# SilentStepStick-TMC2100_v20_5V.net
KiCad netlist of a schematic drawn in EAGLE
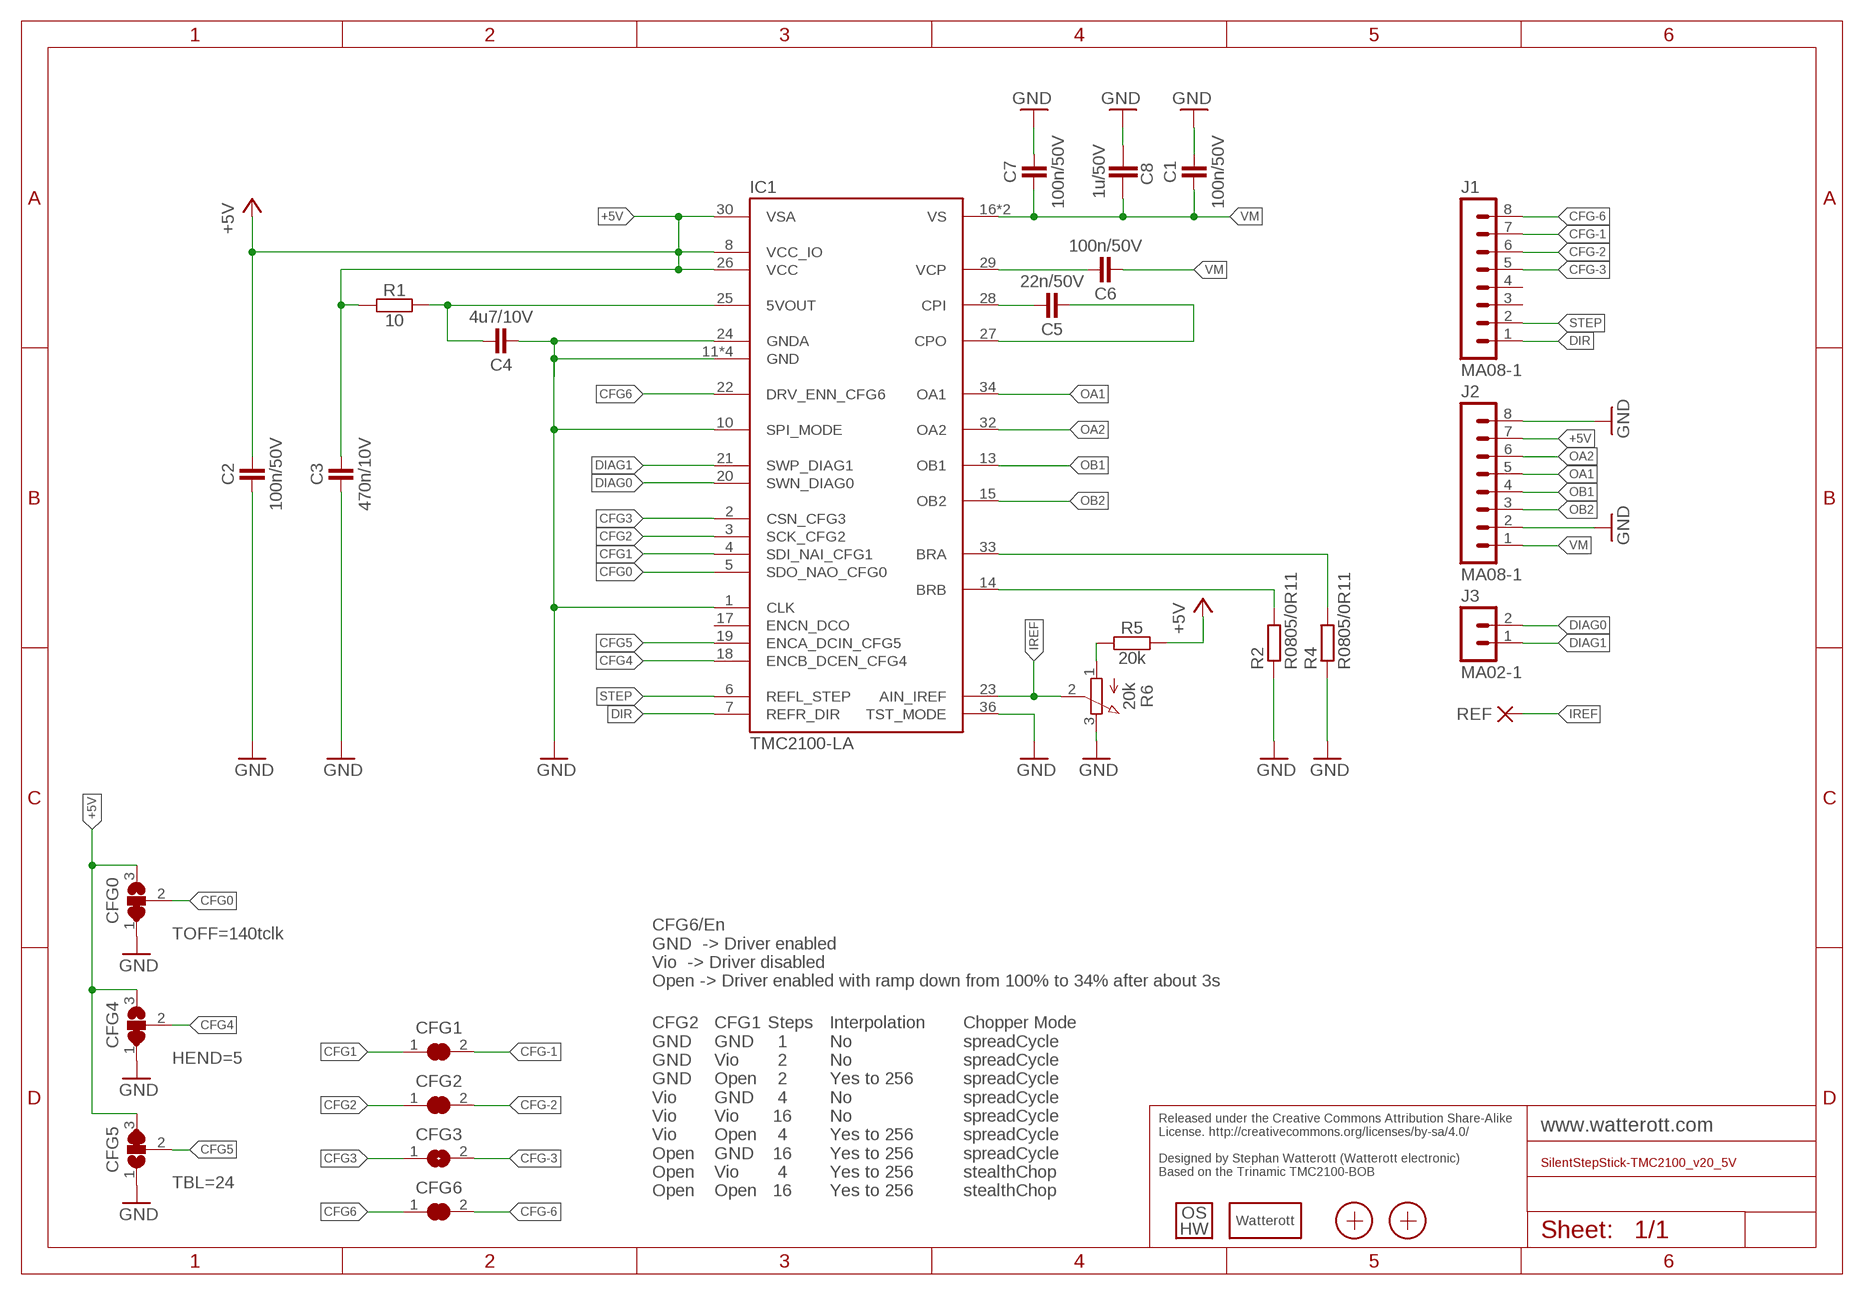
[diagram p0: schematic, sheet 1]

(export (version "E")
  (design (tool "Eeschema 10.0.6"))
  (components
    (comp (ref "C1")
      (value "100n/50V")
      (footprint "eagle-import:C0402")
      (libsource (lib "eagle-import") (part "CAPACITOR-0402"))
    )
    (comp (ref "C2")
      (value "100n/50V")
      (footprint "eagle-import:C0402")
      (libsource (lib "eagle-import") (part "CAPACITOR-0402"))
    )
    (comp (ref "C3")
      (value "470n/10V")
      (footprint "eagle-import:C0402")
      (libsource (lib "eagle-import") (part "CAPACITOR-0402"))
    )
    (comp (ref "C4")
      (value "4u7/10V")
      (footprint "eagle-import:C0402")
      (libsource (lib "eagle-import") (part "CAPACITOR-0402"))
    )
    (comp (ref "C5")
      (value "22n/50V")
      (footprint "eagle-import:C0402")
      (libsource (lib "eagle-import") (part "CAPACITOR-0402"))
    )
    (comp (ref "C6")
      (value "100n/50V")
      (footprint "eagle-import:C0402")
      (libsource (lib "eagle-import") (part "CAPACITOR-0402"))
    )
    (comp (ref "C7")
      (value "100n/50V")
      (footprint "eagle-import:C0402")
      (libsource (lib "eagle-import") (part "CAPACITOR-0402"))
    )
    (comp (ref "C8")
      (value "1u/50V")
      (footprint "eagle-import:C0603")
      (libsource (lib "eagle-import") (part "C-EUC0603"))
    )
    (comp (ref "CFG0")
      (value "JUMPER3-0201")
      (footprint "eagle-import:JUMPER3-0201")
      (libsource (lib "eagle-import") (part "JUMPER3-0201"))
    )
    (comp (ref "CFG1")
      (value "JUMPER2-0201")
      (footprint "eagle-import:JUMPER2-0201")
      (libsource (lib "eagle-import") (part "JUMPER2-0201"))
    )
    (comp (ref "CFG2")
      (value "JUMPER2-0201")
      (footprint "eagle-import:JUMPER2-0201")
      (libsource (lib "eagle-import") (part "JUMPER2-0201"))
    )
    (comp (ref "CFG3")
      (value "JUMPER2-0201")
      (footprint "eagle-import:JUMPER2-0201")
      (libsource (lib "eagle-import") (part "JUMPER2-0201"))
    )
    (comp (ref "CFG4")
      (value "JUMPER3-0201")
      (footprint "eagle-import:JUMPER3-0201")
      (libsource (lib "eagle-import") (part "JUMPER3-0201"))
    )
    (comp (ref "CFG5")
      (value "JUMPER3-0201")
      (footprint "eagle-import:JUMPER3-0201")
      (libsource (lib "eagle-import") (part "JUMPER3-0201"))
    )
    (comp (ref "CFG6")
      (value "JUMPER2-0201")
      (footprint "eagle-import:JUMPER2-0201")
      (libsource (lib "eagle-import") (part "JUMPER2-0201"))
    )
    (comp (ref "IC1")
      (value "TMC2100-LA")
      (footprint "eagle-import:QFN36-PAD")
      (libsource (lib "eagle-import") (part "TMC21X0-LA"))
    )
    (comp (ref "J1")
      (value "MA08-1")
      (footprint "eagle-import:MA08-1")
      (libsource (lib "eagle-import") (part "MA08-1"))
    )
    (comp (ref "J2")
      (value "MA08-1")
      (footprint "eagle-import:MA08-1")
      (libsource (lib "eagle-import") (part "MA08-1"))
    )
    (comp (ref "J3")
      (value "MA02-1")
      (footprint "eagle-import:MA02-1")
      (libsource (lib "eagle-import") (part "MA02-1"))
    )
    (comp (ref "LOGO3")
      (value "LOGO_SPARK-2")
      (footprint "eagle-import:SPARK_2MM")
      (libsource (lib "eagle-import") (part "LOGO_SPARK-2"))
    )
    (comp (ref "LOGO4")
      (value "LOGO_OSHW-2")
      (footprint "eagle-import:OSHW_2MM")
      (libsource (lib "eagle-import") (part "LOGO_OSHW-2"))
    )
    (comp (ref "R1")
      (value "10")
      (footprint "eagle-import:C0402")
      (libsource (lib "eagle-import") (part "RESISTOR-0402"))
    )
    (comp (ref "R2")
      (value "R0805/0R11")
      (footprint "eagle-import:M0805")
      (libsource (lib "eagle-import") (part "R-EU_M0805"))
    )
    (comp (ref "R4")
      (value "R0805/0R11")
      (footprint "eagle-import:M0805")
      (libsource (lib "eagle-import") (part "R-EU_M0805"))
    )
    (comp (ref "R5")
      (value "20k")
      (footprint "eagle-import:C0402")
      (libsource (lib "eagle-import") (part "RESISTOR-0402"))
    )
    (comp (ref "R6")
      (value "20k")
      (footprint "eagle-import:POT_EVM3R")
      (libsource (lib "eagle-import") (part "POT-EVM3R"))
    )
    (comp (ref "REF")
      (value "PAD-0.6-1.1")
      (footprint "eagle-import:PAD-0.6-1.1")
      (libsource (lib "eagle-import") (part "PAD-0.6-1.1"))
    )
    (comp (ref "X1")
      (value "PASSER-07")
      (footprint "eagle-import:PASSER_07MM")
      (libsource (lib "eagle-import") (part "PASSER-07"))
    )
    (comp (ref "X2")
      (value "PASSER-07")
      (footprint "eagle-import:PASSER_07MM")
      (libsource (lib "eagle-import") (part "PASSER-07"))
    )
  )
  (nets
    (net (code "1") (name "+5V") (class "Default")
      (node (ref "C2") (pin "2") (pinfunction "2_2") (pintype "passive"))
      (node (ref "C3") (pin "2") (pinfunction "2_2") (pintype "passive"))
      (node (ref "CFG0") (pin "3") (pinfunction "3_3") (pintype "passive"))
      (node (ref "CFG4") (pin "3") (pinfunction "3_3") (pintype "passive"))
      (node (ref "CFG5") (pin "3") (pinfunction "3_3") (pintype "passive"))
      (node (ref "IC1") (pin "26") (pinfunction "VCC_26") (pintype "power_in"))
      (node (ref "IC1") (pin "30") (pinfunction "VSA_30") (pintype "power_in"))
      (node (ref "IC1") (pin "8") (pinfunction "VCC_IO_8") (pintype "power_in"))
      (node (ref "J2") (pin "7") (pinfunction "7_7") (pintype "passive"))
      (node (ref "R1") (pin "1") (pinfunction "1_1") (pintype "passive"))
      (node (ref "R5") (pin "2") (pinfunction "2_2") (pintype "passive"))
    )
    (net (code "2") (name "CFG-1") (class "Default")
      (node (ref "CFG1") (pin "2") (pinfunction "2_2") (pintype "passive"))
      (node (ref "J1") (pin "7") (pinfunction "7_7") (pintype "passive"))
    )
    (net (code "3") (name "CFG-2") (class "Default")
      (node (ref "CFG2") (pin "2") (pinfunction "2_2") (pintype "passive"))
      (node (ref "J1") (pin "6") (pinfunction "6_6") (pintype "passive"))
    )
    (net (code "4") (name "CFG-3") (class "Default")
      (node (ref "CFG3") (pin "2") (pinfunction "2_2") (pintype "passive"))
      (node (ref "J1") (pin "5") (pinfunction "5_5") (pintype "passive"))
    )
    (net (code "5") (name "CFG-6") (class "Default")
      (node (ref "CFG6") (pin "2") (pinfunction "2_2") (pintype "passive"))
      (node (ref "J1") (pin "8") (pinfunction "8_8") (pintype "passive"))
    )
    (net (code "6") (name "CFG0") (class "Default")
      (node (ref "CFG0") (pin "2") (pinfunction "2_2") (pintype "passive"))
      (node (ref "IC1") (pin "5") (pinfunction "SDO_NAO_CFG0_5") (pintype "bidirectional"))
    )
    (net (code "7") (name "CFG1") (class "Default")
      (node (ref "CFG1") (pin "1") (pinfunction "1_1") (pintype "passive"))
      (node (ref "IC1") (pin "4") (pinfunction "SDI_NAI_CFG1_4") (pintype "bidirectional"))
    )
    (net (code "8") (name "CFG2") (class "Default")
      (node (ref "CFG2") (pin "1") (pinfunction "1_1") (pintype "passive"))
      (node (ref "IC1") (pin "3") (pinfunction "SCK_CFG2_3") (pintype "bidirectional"))
    )
    (net (code "9") (name "CFG3") (class "Default")
      (node (ref "CFG3") (pin "1") (pinfunction "1_1") (pintype "passive"))
      (node (ref "IC1") (pin "2") (pinfunction "CSN_CFG3_2") (pintype "bidirectional"))
    )
    (net (code "10") (name "CFG4") (class "Default")
      (node (ref "CFG4") (pin "2") (pinfunction "2_2") (pintype "passive"))
      (node (ref "IC1") (pin "18") (pinfunction "ENCB_DCEN_CFG4_18") (pintype "bidirectional"))
    )
    (net (code "11") (name "CFG5") (class "Default")
      (node (ref "CFG5") (pin "2") (pinfunction "2_2") (pintype "passive"))
      (node (ref "IC1") (pin "19") (pinfunction "ENCA_DCIN_CFG5_19") (pintype "bidirectional"))
    )
    (net (code "12") (name "CFG6") (class "Default")
      (node (ref "CFG6") (pin "1") (pinfunction "1_1") (pintype "passive"))
      (node (ref "IC1") (pin "22") (pinfunction "DRV_ENN_CFG6_22") (pintype "bidirectional"))
    )
    (net (code "13") (name "DIAG0") (class "Default")
      (node (ref "IC1") (pin "20") (pinfunction "SWN_DIAG0_20") (pintype "bidirectional"))
      (node (ref "J3") (pin "2") (pinfunction "2_2") (pintype "passive"))
    )
    (net (code "14") (name "DIAG1") (class "Default")
      (node (ref "IC1") (pin "21") (pinfunction "SWP_DIAG1_21") (pintype "bidirectional"))
      (node (ref "J3") (pin "1") (pinfunction "1_1") (pintype "passive"))
    )
    (net (code "15") (name "DIR") (class "Default")
      (node (ref "IC1") (pin "7") (pinfunction "REFR_DIR_7") (pintype "bidirectional"))
      (node (ref "J1") (pin "1") (pinfunction "1_1") (pintype "passive"))
    )
    (net (code "16") (name "GND") (class "Default")
      (node (ref "C1") (pin "2") (pinfunction "2_2") (pintype "passive"))
      (node (ref "C2") (pin "1") (pinfunction "1_1") (pintype "passive"))
      (node (ref "C3") (pin "1") (pinfunction "1_1") (pintype "passive"))
      (node (ref "C4") (pin "1") (pinfunction "1_1") (pintype "passive"))
      (node (ref "C7") (pin "2") (pinfunction "2_2") (pintype "passive"))
      (node (ref "C8") (pin "2") (pinfunction "2_2") (pintype "passive"))
      (node (ref "CFG0") (pin "1") (pinfunction "1_1") (pintype "passive"))
      (node (ref "CFG4") (pin "1") (pinfunction "1_1") (pintype "passive"))
      (node (ref "CFG5") (pin "1") (pinfunction "1_1") (pintype "passive"))
      (node (ref "IC1") (pin "1") (pinfunction "CLK_1") (pintype "bidirectional"))
      (node (ref "IC1") (pin "10") (pinfunction "SPI_MODE_10") (pintype "bidirectional"))
      (node (ref "IC1") (pin "11") (pinfunction "GND_11") (pintype "power_in"))
      (node (ref "IC1") (pin "12") (pinfunction "GND_12") (pintype "power_in"))
      (node (ref "IC1") (pin "24") (pinfunction "GNDA_24") (pintype "power_in"))
      (node (ref "IC1") (pin "35") (pinfunction "GND_35") (pintype "power_in"))
      (node (ref "IC1") (pin "36") (pinfunction "TST_MODE_36") (pintype "bidirectional"))
      (node (ref "IC1") (pin "TP") (pinfunction "GND_TP") (pintype "power_in"))
      (node (ref "J2") (pin "2") (pinfunction "2_2") (pintype "passive"))
      (node (ref "J2") (pin "8") (pinfunction "8_8") (pintype "passive"))
      (node (ref "R2") (pin "1") (pinfunction "1_1") (pintype "passive"))
      (node (ref "R4") (pin "1") (pinfunction "1_1") (pintype "passive"))
      (node (ref "R6") (pin "3") (pinfunction "E_3") (pintype "passive"))
    )
    (net (code "17") (name "IREF") (class "Default")
      (node (ref "IC1") (pin "23") (pinfunction "AIN_IREF_23") (pintype "passive"))
      (node (ref "R6") (pin "2") (pinfunction "S_2") (pintype "passive"))
      (node (ref "REF") (pin "1") (pinfunction "P_1") (pintype "passive"))
    )
    (net (code "18") (name "Net-(IC1-5VOUT)") (class "Default")
      (node (ref "C4") (pin "2") (pinfunction "2_2") (pintype "passive"))
      (node (ref "IC1") (pin "25") (pinfunction "5VOUT_25") (pintype "power_in"))
      (node (ref "R1") (pin "2") (pinfunction "2_2") (pintype "passive"))
    )
    (net (code "19") (name "Net-(IC1-BRA)") (class "Default")
      (node (ref "IC1") (pin "33") (pinfunction "BRA_33") (pintype "output"))
      (node (ref "R4") (pin "2") (pinfunction "2_2") (pintype "passive"))
    )
    (net (code "20") (name "Net-(IC1-BRB)") (class "Default")
      (node (ref "IC1") (pin "14") (pinfunction "BRB_14") (pintype "output"))
      (node (ref "R2") (pin "2") (pinfunction "2_2") (pintype "passive"))
    )
    (net (code "21") (name "Net-(IC1-CPI)") (class "Default")
      (node (ref "C5") (pin "2") (pinfunction "2_2") (pintype "passive"))
      (node (ref "IC1") (pin "28") (pinfunction "CPI_28") (pintype "passive"))
    )
    (net (code "22") (name "Net-(IC1-CPO)") (class "Default")
      (node (ref "C5") (pin "1") (pinfunction "1_1") (pintype "passive"))
      (node (ref "IC1") (pin "27") (pinfunction "CPO_27") (pintype "passive"))
    )
    (net (code "23") (name "Net-(IC1-VCP)") (class "Default")
      (node (ref "C6") (pin "2") (pinfunction "2_2") (pintype "passive"))
      (node (ref "IC1") (pin "29") (pinfunction "VCP_29") (pintype "passive"))
    )
    (net (code "24") (name "Net-(R6-A)") (class "Default")
      (node (ref "R5") (pin "1") (pinfunction "1_1") (pintype "passive"))
      (node (ref "R6") (pin "1") (pinfunction "A_1") (pintype "passive"))
    )
    (net (code "25") (name "OA1") (class "Default")
      (node (ref "IC1") (pin "34") (pinfunction "OA1_34") (pintype "output"))
      (node (ref "J2") (pin "5") (pinfunction "5_5") (pintype "passive"))
    )
    (net (code "26") (name "OA2") (class "Default")
      (node (ref "IC1") (pin "32") (pinfunction "OA2_32") (pintype "output"))
      (node (ref "J2") (pin "6") (pinfunction "6_6") (pintype "passive"))
    )
    (net (code "27") (name "OB1") (class "Default")
      (node (ref "IC1") (pin "13") (pinfunction "OB1_13") (pintype "output"))
      (node (ref "J2") (pin "4") (pinfunction "4_4") (pintype "passive"))
    )
    (net (code "28") (name "OB2") (class "Default")
      (node (ref "IC1") (pin "15") (pinfunction "OB2_15") (pintype "output"))
      (node (ref "J2") (pin "3") (pinfunction "3_3") (pintype "passive"))
    )
    (net (code "29") (name "STEP") (class "Default")
      (node (ref "IC1") (pin "6") (pinfunction "REFL_STEP_6") (pintype "bidirectional"))
      (node (ref "J1") (pin "2") (pinfunction "2_2") (pintype "passive"))
    )
    (net (code "30") (name "VM") (class "Default")
      (node (ref "C1") (pin "1") (pinfunction "1_1") (pintype "passive"))
      (node (ref "C6") (pin "1") (pinfunction "1_1") (pintype "passive"))
      (node (ref "C7") (pin "1") (pinfunction "1_1") (pintype "passive"))
      (node (ref "C8") (pin "1") (pinfunction "1_1") (pintype "passive"))
      (node (ref "IC1") (pin "16") (pinfunction "VS_16") (pintype "power_in"))
      (node (ref "IC1") (pin "31") (pinfunction "VS_31") (pintype "power_in"))
      (node (ref "J2") (pin "1") (pinfunction "1_1") (pintype "passive"))
    )
    (net (code "31") (name "unconnected-(IC1-ENCN_DCO-Pad17)") (class "Default")
      (node (ref "IC1") (pin "17") (pinfunction "ENCN_DCO_17") (pintype "bidirectional"))
    )
    (net (code "32") (name "unconnected-(J1-Pad3)") (class "Default")
      (node (ref "J1") (pin "3") (pinfunction "3_3") (pintype "passive"))
    )
    (net (code "33") (name "unconnected-(J1-Pad4)") (class "Default")
      (node (ref "J1") (pin "4") (pinfunction "4_4") (pintype "passive"))
    )
  )
)
